# LittleButtons.net
KiCad netlist of a schematic drawn in Altium Designer
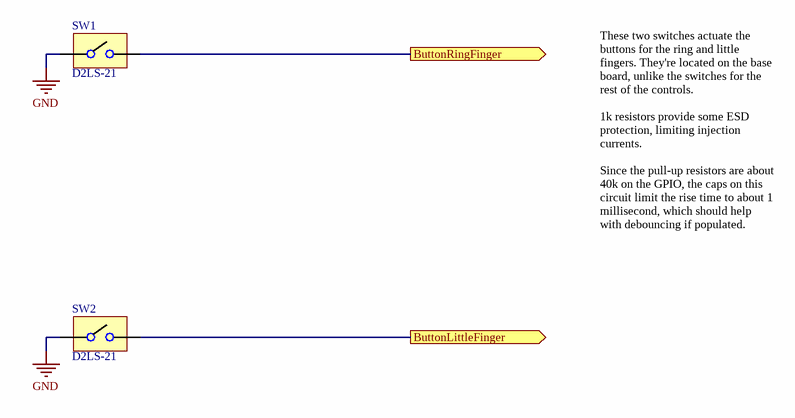
[diagram p0: LittleButtons.SchDoc]

(export (version "E")
  (design (tool "Eeschema 10.0.6"))
  (components
    (comp (ref "SW1")
      (value "D2LS-21")
      (footprint "D2LS-21")
      (description "Compact Surface-mounting Switch for long durability")
      (libsource (lib "Switches") (part "D2LS-21"))
    )
    (comp (ref "SW2")
      (value "D2LS-21")
      (footprint "D2LS-21")
      (description "Compact Surface-mounting Switch for long durability")
      (libsource (lib "Switches") (part "D2LS-21"))
    )
  )
  (nets
    (net (code "1") (name "/ButtonLittleFinger") (class "Default")
      (node (ref "SW2") (pin "B") (pinfunction "B_B") (pintype "passive"))
    )
    (net (code "2") (name "/ButtonRingFinger") (class "Default")
      (node (ref "SW1") (pin "B") (pinfunction "B_B") (pintype "passive"))
    )
    (net (code "3") (name "GND") (class "Default")
      (node (ref "SW1") (pin "A") (pinfunction "A_A") (pintype "passive"))
      (node (ref "SW2") (pin "A") (pinfunction "A_A") (pintype "passive"))
    )
  )
)
